# DXP.net
KiCad netlist of a schematic drawn in Altium Designer
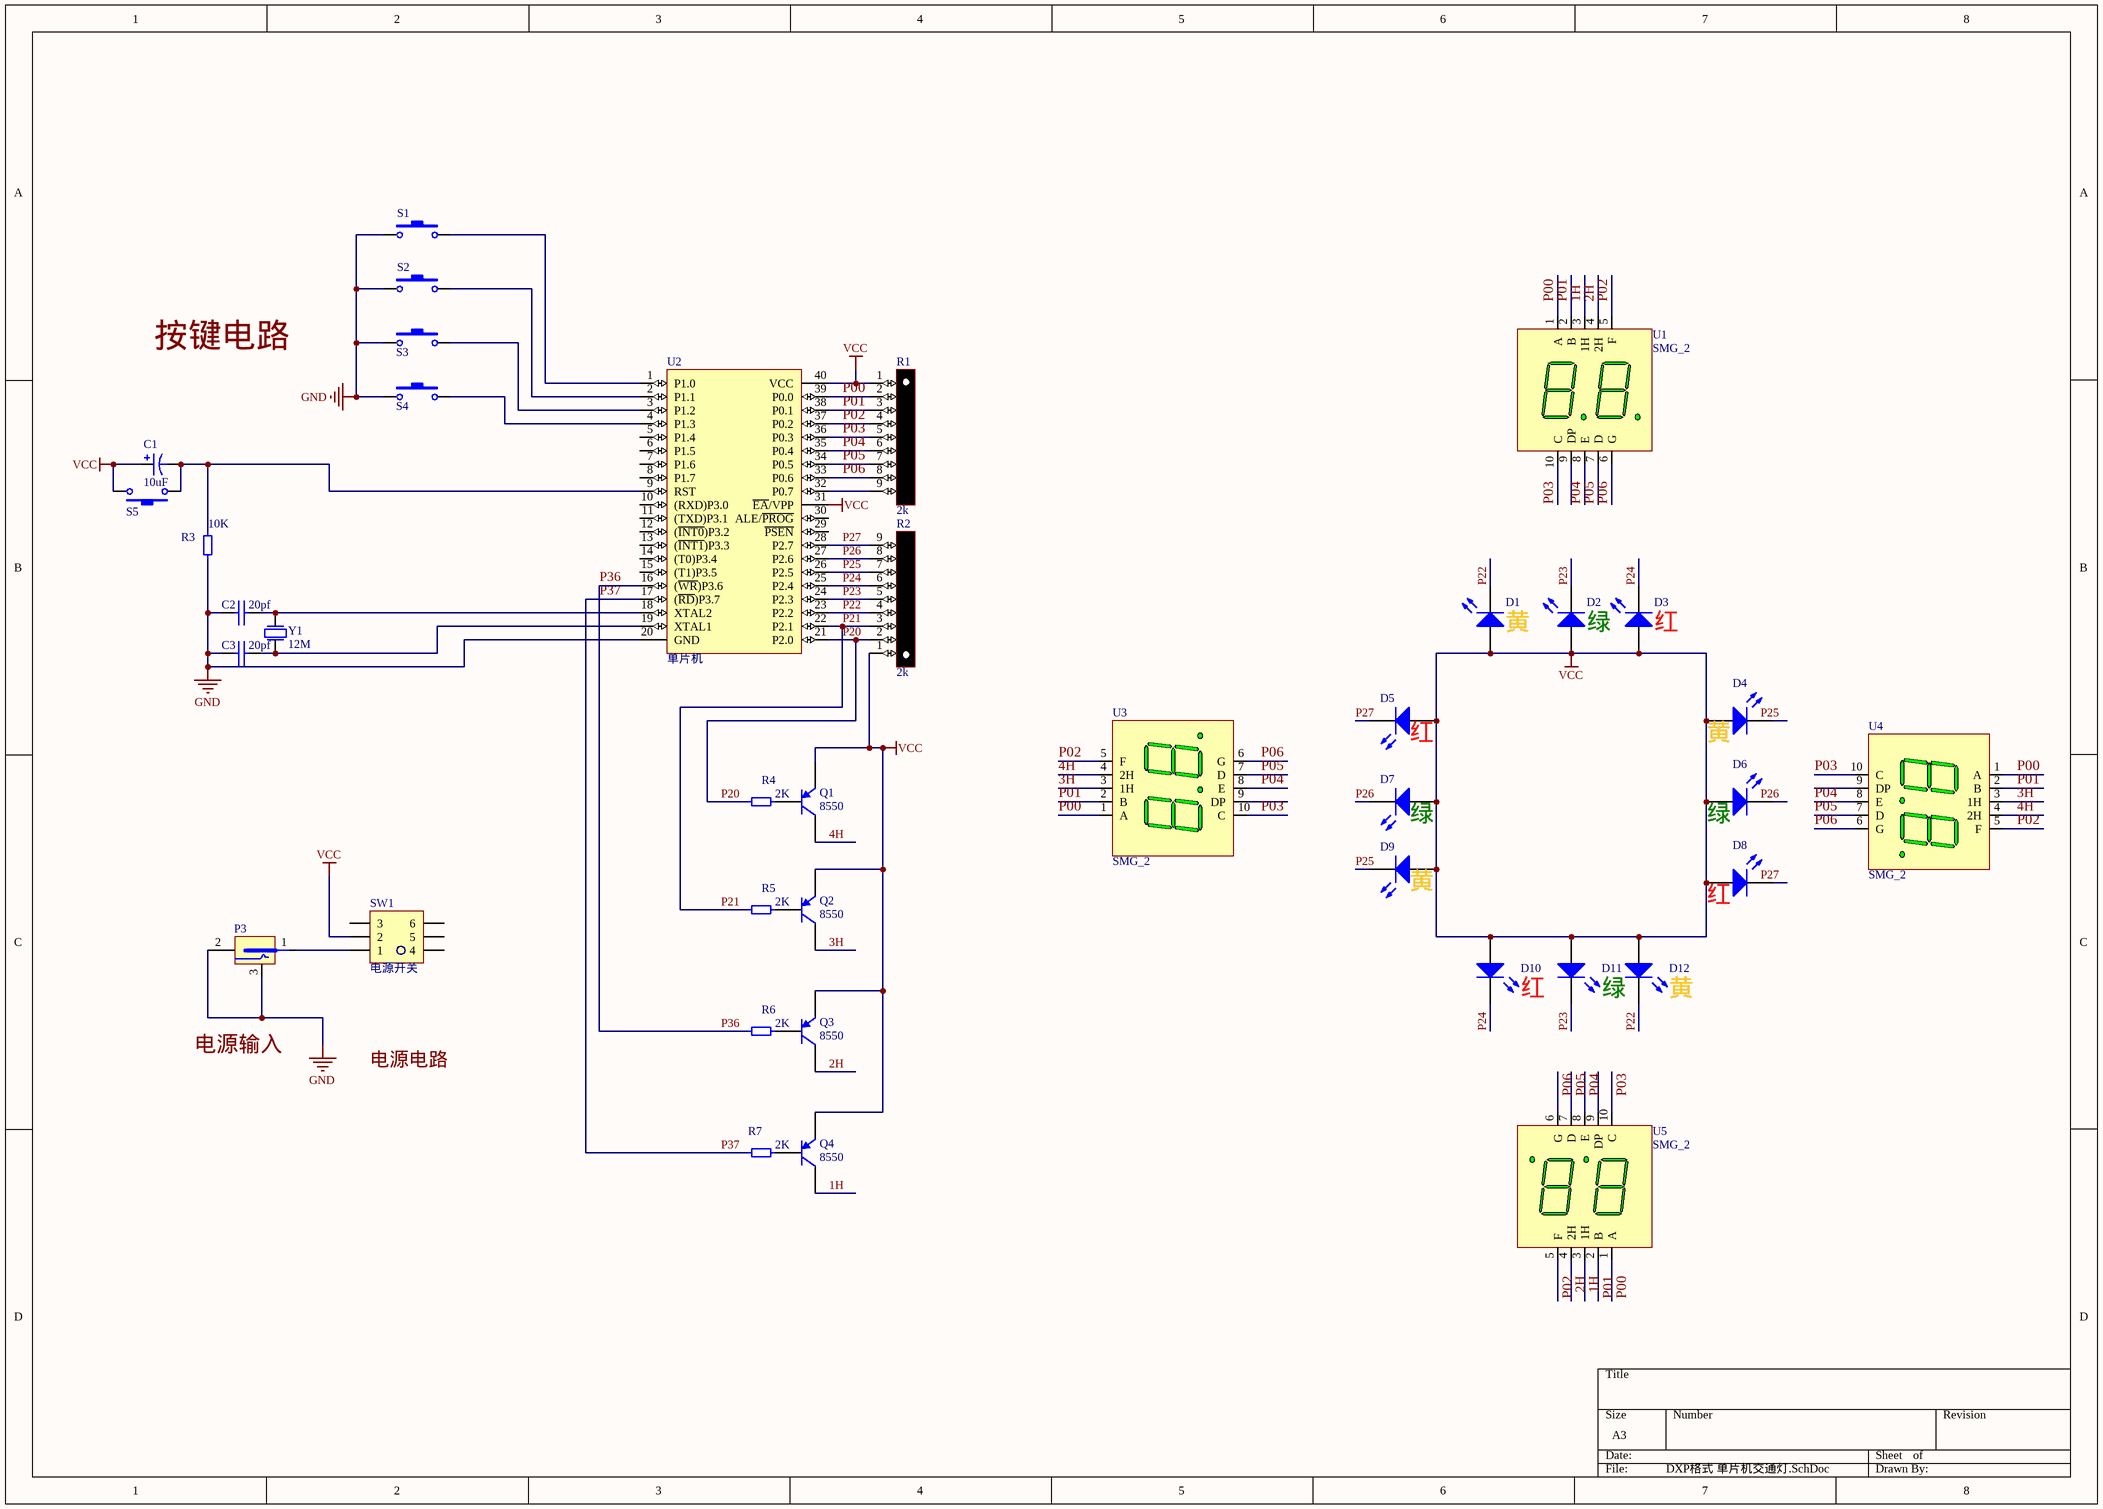
[diagram p0: DXP格式 单片机交通灯.SchDoc]

(export (version "E")
  (design (tool "Eeschema 10.0.6"))
  (components
    (comp (ref "C1")
      (value "10uF")
      (footprint "C_10")
      (description "Polarized Capacitor (Radial)")
      (fields (field (name "PUBLISHER") "Altium Limited"))
      (libsource (lib "简易动环监控系统") (part "Cap Pol1"))
    )
    (comp (ref "C2")
      (value "20pf")
      (footprint "CAP CP")
      (description "电容")
      (libsource (lib "C8051F020最小2") (part "CAP"))
    )
    (comp (ref "C3")
      (value "20pf")
      (footprint "CAP CP")
      (description "电容")
      (libsource (lib "C8051F020最小2") (part "CAP"))
    )
    (comp (ref "D1") (value "黄") (footprint "LED2J") (description "发光二极管") (libsource (lib "亮") (part "LED")))
    (comp (ref "D2") (value "绿") (footprint "LED2J") (description "发光二极管") (libsource (lib "亮") (part "LED")))
    (comp (ref "D3") (value "红") (footprint "LED2J") (description "发光二极管") (libsource (lib "亮") (part "LED")))
    (comp (ref "D4") (value "黄") (footprint "LED2J") (description "发光二极管") (libsource (lib "亮") (part "LED")))
    (comp (ref "D5") (value "红") (footprint "LED2J") (description "发光二极管") (libsource (lib "亮") (part "LED")))
    (comp (ref "D6") (value "绿") (footprint "LED2J") (description "发光二极管") (libsource (lib "亮") (part "LED")))
    (comp (ref "D7") (value "绿") (footprint "LED2J") (description "发光二极管") (libsource (lib "亮") (part "LED")))
    (comp (ref "D8") (value "红") (footprint "LED2J") (description "发光二极管") (libsource (lib "亮") (part "LED")))
    (comp (ref "D9") (value "黄") (footprint "LED2J") (description "发光二极管") (libsource (lib "亮") (part "LED")))
    (comp (ref "D10")
      (value "红")
      (footprint "LED2J")
      (description "发光二极管")
      (libsource (lib "亮") (part "LED"))
    )
    (comp (ref "D11")
      (value "绿")
      (footprint "LED2J")
      (description "发光二极管")
      (libsource (lib "亮") (part "LED"))
    )
    (comp (ref "D12")
      (value "黄")
      (footprint "LED2J")
      (description "发光二极管")
      (libsource (lib "亮") (part "LED"))
    )
    (comp (ref "P3") (value "电源输入") (footprint "DC2.1") (libsource (lib "我自己的") (part "POWER")))
    (comp (ref "Q1")
      (value "8550")
      (footprint "s三极管直插")
      (description "PNP General Purpose Amplifier")
      (fields (field (name "PUBLISHER") "Altium Limited"))
      (libsource (lib "Miscellaneous Devices") (part "2N3906"))
    )
    (comp (ref "Q2")
      (value "8550")
      (footprint "s三极管直插")
      (description "PNP General Purpose Amplifier")
      (fields (field (name "PUBLISHER") "Altium Limited"))
      (libsource (lib "Miscellaneous Devices") (part "2N3906"))
    )
    (comp (ref "Q3")
      (value "8550")
      (footprint "s三极管直插")
      (description "PNP General Purpose Amplifier")
      (fields (field (name "PUBLISHER") "Altium Limited"))
      (libsource (lib "Miscellaneous Devices") (part "2N3906"))
    )
    (comp (ref "Q4")
      (value "8550")
      (footprint "s三极管直插")
      (description "PNP General Purpose Amplifier")
      (fields (field (name "PUBLISHER") "Altium Limited"))
      (libsource (lib "Miscellaneous Devices") (part "2N3906"))
    )
    (comp (ref "R1") (value "2k") (footprint "SIP9") (description "排阻") (libsource (lib "") (part "RES9_1")))
    (comp (ref "R2") (value "2k") (footprint "SIP9") (description "排阻") (libsource (lib "亮") (part "RES9")))
    (comp (ref "R3") (value "10K") (footprint "AXIAL0.3") (libsource (lib "C8051F020最小2") (part "RES2")))
    (comp (ref "R4") (value "2K") (footprint "AXIAL0.3") (libsource (lib "C8051F020最小2") (part "RES2")))
    (comp (ref "R5") (value "2K") (footprint "AXIAL0.3") (libsource (lib "C8051F020最小2") (part "RES2")))
    (comp (ref "R6") (value "2K") (footprint "AXIAL0.3") (libsource (lib "C8051F020最小2") (part "RES2")))
    (comp (ref "R7") (value "2K") (footprint "AXIAL0.3") (libsource (lib "C8051F020最小2") (part "RES2")))
    (comp (ref "S1")
      (value "SW-PB")
      (footprint "key")
      (description "Switch")
      (fields (field (name "PUBLISHER") "Altium Limited"))
      (libsource (lib "实验板原理图") (part "SW-PB"))
    )
    (comp (ref "S2")
      (value "SW-PB")
      (footprint "key")
      (description "Switch")
      (fields (field (name "PUBLISHER") "Altium Limited"))
      (libsource (lib "实验板原理图") (part "SW-PB"))
    )
    (comp (ref "S3")
      (value "SW-PB")
      (footprint "key")
      (description "Switch")
      (fields (field (name "PUBLISHER") "Altium Limited"))
      (libsource (lib "实验板原理图") (part "SW-PB"))
    )
    (comp (ref "S4")
      (value "SW-PB")
      (footprint "key")
      (description "Switch")
      (fields (field (name "PUBLISHER") "Altium Limited"))
      (libsource (lib "实验板原理图") (part "SW-PB"))
    )
    (comp (ref "S5")
      (value "SW-PB")
      (footprint "key")
      (description "Switch")
      (fields (field (name "PUBLISHER") "Altium Limited"))
      (libsource (lib "实验板原理图") (part "SW-PB"))
    )
    (comp (ref "SW1") (value "电源开关") (footprint "sw_自锁 1") (libsource (lib "我自己的") (part "SW1")))
    (comp (ref "U1") (value "SMG_2") (footprint "SMG_2") (libsource (lib "") (part "SMG_2_2")))
    (comp (ref "U2") (value "单片机") (footprint "DIP40 - 做板") (libsource (lib "实验板原理图") (part "U1")))
    (comp (ref "U3") (value "SMG_2") (footprint "SMG_2") (libsource (lib "") (part "SMG_2_3")))
    (comp (ref "U4") (value "SMG_2") (footprint "SMG_2") (libsource (lib "") (part "SMG_2_1")))
    (comp (ref "U5") (value "SMG_2") (footprint "SMG_2") (libsource (lib "交通灯+上下班高峰调整") (part "SMG_2")))
    (comp (ref "Y1")
      (value "12M")
      (footprint "XTAL")
      (description "Crystal Oscillator")
      (libsource (lib "C8051F020最小2") (part "16M"))
    )
  )
  (nets
    (net (code "1") (name "/1H") (class "Default")
      (node (ref "Q4") (pin "3") (pinfunction "C_3") (pintype "passive"))
      (node (ref "U1") (pin "3") (pinfunction "1H_3") (pintype "passive"))
      (node (ref "U5") (pin "3") (pinfunction "1H_3") (pintype "passive"))
    )
    (net (code "2") (name "/2H") (class "Default")
      (node (ref "Q3") (pin "3") (pinfunction "C_3") (pintype "passive"))
      (node (ref "U1") (pin "4") (pinfunction "2H_4") (pintype "passive"))
      (node (ref "U5") (pin "4") (pinfunction "2H_4") (pintype "passive"))
    )
    (net (code "3") (name "/3H") (class "Default")
      (node (ref "Q2") (pin "3") (pinfunction "C_3") (pintype "passive"))
      (node (ref "U3") (pin "3") (pinfunction "1H_3") (pintype "passive"))
      (node (ref "U4") (pin "3") (pinfunction "1H_3") (pintype "passive"))
    )
    (net (code "4") (name "/4H") (class "Default")
      (node (ref "Q1") (pin "3") (pinfunction "C_3") (pintype "passive"))
      (node (ref "U3") (pin "4") (pinfunction "2H_4") (pintype "passive"))
      (node (ref "U4") (pin "4") (pinfunction "2H_4") (pintype "passive"))
    )
    (net (code "5") (name "/P00") (class "Default")
      (node (ref "R1") (pin "2") (pinfunction "2_2") (pintype "bidirectional"))
      (node (ref "U1") (pin "1") (pinfunction "A_1") (pintype "passive"))
      (node (ref "U2") (pin "39") (pinfunction "P0.0_39") (pintype "bidirectional"))
      (node (ref "U3") (pin "1") (pinfunction "A_1") (pintype "passive"))
      (node (ref "U4") (pin "1") (pinfunction "A_1") (pintype "passive"))
      (node (ref "U5") (pin "1") (pinfunction "A_1") (pintype "passive"))
    )
    (net (code "6") (name "/P01") (class "Default")
      (node (ref "R1") (pin "3") (pinfunction "3_3") (pintype "bidirectional"))
      (node (ref "U1") (pin "2") (pinfunction "B_2") (pintype "passive"))
      (node (ref "U2") (pin "38") (pinfunction "P0.1_38") (pintype "bidirectional"))
      (node (ref "U3") (pin "2") (pinfunction "B_2") (pintype "passive"))
      (node (ref "U4") (pin "2") (pinfunction "B_2") (pintype "passive"))
      (node (ref "U5") (pin "2") (pinfunction "B_2") (pintype "passive"))
    )
    (net (code "7") (name "/P02") (class "Default")
      (node (ref "R1") (pin "4") (pinfunction "4_4") (pintype "bidirectional"))
      (node (ref "U1") (pin "5") (pinfunction "F_5") (pintype "passive"))
      (node (ref "U2") (pin "37") (pinfunction "P0.2_37") (pintype "bidirectional"))
      (node (ref "U3") (pin "5") (pinfunction "F_5") (pintype "passive"))
      (node (ref "U4") (pin "5") (pinfunction "F_5") (pintype "passive"))
      (node (ref "U5") (pin "5") (pinfunction "F_5") (pintype "passive"))
    )
    (net (code "8") (name "/P03") (class "Default")
      (node (ref "R1") (pin "5") (pinfunction "5_5") (pintype "bidirectional"))
      (node (ref "U1") (pin "10") (pinfunction "C_10") (pintype "passive"))
      (node (ref "U2") (pin "36") (pinfunction "P0.3_36") (pintype "bidirectional"))
      (node (ref "U3") (pin "10") (pinfunction "C_10") (pintype "passive"))
      (node (ref "U4") (pin "10") (pinfunction "C_10") (pintype "passive"))
      (node (ref "U5") (pin "10") (pinfunction "C_10") (pintype "passive"))
    )
    (net (code "9") (name "/P04") (class "Default")
      (node (ref "R1") (pin "6") (pinfunction "6_6") (pintype "bidirectional"))
      (node (ref "U1") (pin "8") (pinfunction "E_8") (pintype "passive"))
      (node (ref "U2") (pin "35") (pinfunction "P0.4_35") (pintype "bidirectional"))
      (node (ref "U3") (pin "8") (pinfunction "E_8") (pintype "passive"))
      (node (ref "U4") (pin "8") (pinfunction "E_8") (pintype "passive"))
      (node (ref "U5") (pin "8") (pinfunction "E_8") (pintype "passive"))
    )
    (net (code "10") (name "/P05") (class "Default")
      (node (ref "R1") (pin "7") (pinfunction "7_7") (pintype "bidirectional"))
      (node (ref "U1") (pin "7") (pinfunction "D_7") (pintype "passive"))
      (node (ref "U2") (pin "34") (pinfunction "P0.5_34") (pintype "bidirectional"))
      (node (ref "U3") (pin "7") (pinfunction "D_7") (pintype "passive"))
      (node (ref "U4") (pin "7") (pinfunction "D_7") (pintype "passive"))
      (node (ref "U5") (pin "7") (pinfunction "D_7") (pintype "passive"))
    )
    (net (code "11") (name "/P06") (class "Default")
      (node (ref "R1") (pin "8") (pinfunction "8_8") (pintype "bidirectional"))
      (node (ref "U1") (pin "6") (pinfunction "G_6") (pintype "passive"))
      (node (ref "U2") (pin "33") (pinfunction "P0.6_33") (pintype "bidirectional"))
      (node (ref "U3") (pin "6") (pinfunction "G_6") (pintype "passive"))
      (node (ref "U4") (pin "6") (pinfunction "G_6") (pintype "passive"))
      (node (ref "U5") (pin "6") (pinfunction "G_6") (pintype "passive"))
    )
    (net (code "12") (name "/P20") (class "Default")
      (node (ref "R2") (pin "2") (pinfunction "2_2") (pintype "bidirectional"))
      (node (ref "R2") (pin "3") (pinfunction "3_3") (pintype "bidirectional"))
      (node (ref "R4") (pin "2") (pinfunction "2_2") (pintype "passive"))
      (node (ref "R5") (pin "2") (pinfunction "2_2") (pintype "passive"))
      (node (ref "U2") (pin "21") (pinfunction "P2.0_21") (pintype "bidirectional"))
      (node (ref "U2") (pin "22") (pinfunction "P2.1_22") (pintype "bidirectional"))
    )
    (net (code "13") (name "/P22") (class "Default")
      (node (ref "D1") (pin "2") (pinfunction "K_2") (pintype "passive"))
      (node (ref "D12") (pin "2") (pinfunction "K_2") (pintype "passive"))
      (node (ref "R2") (pin "4") (pinfunction "4_4") (pintype "bidirectional"))
      (node (ref "U2") (pin "23") (pinfunction "P2.2_23") (pintype "bidirectional"))
    )
    (net (code "14") (name "/P23") (class "Default")
      (node (ref "D11") (pin "2") (pinfunction "K_2") (pintype "passive"))
      (node (ref "D2") (pin "2") (pinfunction "K_2") (pintype "passive"))
      (node (ref "R2") (pin "5") (pinfunction "5_5") (pintype "bidirectional"))
      (node (ref "U2") (pin "24") (pinfunction "P2.3_24") (pintype "bidirectional"))
    )
    (net (code "15") (name "/P24") (class "Default")
      (node (ref "D10") (pin "2") (pinfunction "K_2") (pintype "passive"))
      (node (ref "D3") (pin "2") (pinfunction "K_2") (pintype "passive"))
      (node (ref "R2") (pin "6") (pinfunction "6_6") (pintype "bidirectional"))
      (node (ref "U2") (pin "25") (pinfunction "P2.4_25") (pintype "bidirectional"))
    )
    (net (code "16") (name "/P25") (class "Default")
      (node (ref "D9") (pin "2") (pinfunction "K_2") (pintype "passive"))
      (node (ref "R2") (pin "7") (pinfunction "7_7") (pintype "bidirectional"))
      (node (ref "U2") (pin "26") (pinfunction "P2.5_26") (pintype "bidirectional"))
    )
    (net (code "17") (name "/P26") (class "Default")
      (node (ref "D7") (pin "2") (pinfunction "K_2") (pintype "passive"))
      (node (ref "R2") (pin "8") (pinfunction "8_8") (pintype "bidirectional"))
      (node (ref "U2") (pin "27") (pinfunction "P2.6_27") (pintype "bidirectional"))
    )
    (net (code "18") (name "/P27") (class "Default")
      (node (ref "D5") (pin "2") (pinfunction "K_2") (pintype "passive"))
      (node (ref "R2") (pin "9") (pinfunction "9_9") (pintype "bidirectional"))
      (node (ref "U2") (pin "28") (pinfunction "P2.7_28") (pintype "bidirectional"))
    )
    (net (code "19") (name "/P36") (class "Default")
      (node (ref "R6") (pin "2") (pinfunction "2_2") (pintype "passive"))
      (node (ref "R7") (pin "2") (pinfunction "2_2") (pintype "passive"))
      (node (ref "U2") (pin "16") (pinfunction "(~{WR})P3.6_16") (pintype "bidirectional"))
      (node (ref "U2") (pin "17") (pinfunction "(~{RD})P3.7_17") (pintype "bidirectional"))
    )
    (net (code "23") (name "GND") (class "Default")
      (node (ref "C2") (pin "1") (pinfunction "1_1") (pintype "passive"))
      (node (ref "C3") (pin "1") (pinfunction "1_1") (pintype "passive"))
      (node (ref "P3") (pin "2") (pintype "passive"))
      (node (ref "P3") (pin "3") (pintype "passive"))
      (node (ref "R3") (pin "1") (pinfunction "1_1") (pintype "passive"))
      (node (ref "S1") (pin "2") (pinfunction "2_2") (pintype "passive"))
      (node (ref "S2") (pin "2") (pinfunction "2_2") (pintype "passive"))
      (node (ref "S3") (pin "2") (pinfunction "2_2") (pintype "passive"))
      (node (ref "S4") (pin "2") (pinfunction "2_2") (pintype "passive"))
      (node (ref "U2") (pin "20") (pinfunction "GND_20") (pintype "power_in"))
    )
    (net (code "24") (name "Net-(P3-Pad1)") (class "Default")
      (node (ref "P3") (pin "1") (pintype "passive"))
      (node (ref "SW1") (pin "1") (pinfunction "1_1") (pintype "passive"))
    )
    (net (code "25") (name "Net-(Q1-B)") (class "Default")
      (node (ref "Q1") (pin "2") (pinfunction "B_2") (pintype "passive"))
      (node (ref "R4") (pin "1") (pinfunction "1_1") (pintype "passive"))
    )
    (net (code "26") (name "Net-(Q2-B)") (class "Default")
      (node (ref "Q2") (pin "2") (pinfunction "B_2") (pintype "passive"))
      (node (ref "R5") (pin "1") (pinfunction "1_1") (pintype "passive"))
    )
    (net (code "27") (name "Net-(Q3-B)") (class "Default")
      (node (ref "Q3") (pin "2") (pinfunction "B_2") (pintype "passive"))
      (node (ref "R6") (pin "1") (pinfunction "1_1") (pintype "passive"))
    )
    (net (code "28") (name "Net-(Q4-B)") (class "Default")
      (node (ref "Q4") (pin "2") (pinfunction "B_2") (pintype "passive"))
      (node (ref "R7") (pin "1") (pinfunction "1_1") (pintype "passive"))
    )
    (net (code "29") (name "Net-(U2-P0.7)") (class "Default")
      (node (ref "R1") (pin "9") (pinfunction "9_9") (pintype "bidirectional"))
      (node (ref "U2") (pin "32") (pinfunction "P0.7_32") (pintype "bidirectional"))
    )
    (net (code "30") (name "Net-(U2-P1.0)") (class "Default")
      (node (ref "S1") (pin "1") (pinfunction "1_1") (pintype "passive"))
      (node (ref "U2") (pin "1") (pinfunction "P1.0_1") (pintype "bidirectional"))
    )
    (net (code "31") (name "Net-(U2-P1.1)") (class "Default")
      (node (ref "S2") (pin "1") (pinfunction "1_1") (pintype "passive"))
      (node (ref "U2") (pin "2") (pinfunction "P1.1_2") (pintype "bidirectional"))
    )
    (net (code "32") (name "Net-(U2-P1.2)") (class "Default")
      (node (ref "S3") (pin "1") (pinfunction "1_1") (pintype "passive"))
      (node (ref "U2") (pin "3") (pinfunction "P1.2_3") (pintype "bidirectional"))
    )
    (net (code "33") (name "Net-(U2-P1.3)") (class "Default")
      (node (ref "S4") (pin "1") (pinfunction "1_1") (pintype "passive"))
      (node (ref "U2") (pin "4") (pinfunction "P1.3_4") (pintype "bidirectional"))
    )
    (net (code "34") (name "Net-(U2-RST)") (class "Default")
      (node (ref "C1") (pin "2") (pinfunction "2_2") (pintype "passive"))
      (node (ref "R3") (pin "2") (pinfunction "2_2") (pintype "passive"))
      (node (ref "S5") (pin "1") (pinfunction "1_1") (pintype "passive"))
      (node (ref "U2") (pin "9") (pinfunction "RST_9") (pintype "bidirectional"))
    )
    (net (code "35") (name "Net-(U2-XTAL1)") (class "Default")
      (node (ref "C3") (pin "2") (pinfunction "2_2") (pintype "passive"))
      (node (ref "U2") (pin "19") (pinfunction "XTAL1_19") (pintype "bidirectional"))
      (node (ref "Y1") (pin "2") (pinfunction "P2_2") (pintype "passive"))
    )
    (net (code "36") (name "Net-(U2-XTAL2)") (class "Default")
      (node (ref "C2") (pin "2") (pinfunction "2_2") (pintype "passive"))
      (node (ref "U2") (pin "18") (pinfunction "XTAL2_18") (pintype "bidirectional"))
      (node (ref "Y1") (pin "1") (pinfunction "P1_1") (pintype "passive"))
    )
    (net (code "37") (name "VCC") (class "Default")
      (node (ref "C1") (pin "1") (pinfunction "1_1") (pintype "passive"))
      (node (ref "D1") (pin "1") (pinfunction "A_1") (pintype "passive"))
      (node (ref "D10") (pin "1") (pinfunction "A_1") (pintype "passive"))
      (node (ref "D11") (pin "1") (pinfunction "A_1") (pintype "passive"))
      (node (ref "D12") (pin "1") (pinfunction "A_1") (pintype "passive"))
      (node (ref "D2") (pin "1") (pinfunction "A_1") (pintype "passive"))
      (node (ref "D3") (pin "1") (pinfunction "A_1") (pintype "passive"))
      (node (ref "D4") (pin "1") (pinfunction "A_1") (pintype "passive"))
      (node (ref "D5") (pin "1") (pinfunction "A_1") (pintype "passive"))
      (node (ref "D6") (pin "1") (pinfunction "A_1") (pintype "passive"))
      (node (ref "D7") (pin "1") (pinfunction "A_1") (pintype "passive"))
      (node (ref "D8") (pin "1") (pinfunction "A_1") (pintype "passive"))
      (node (ref "D9") (pin "1") (pinfunction "A_1") (pintype "passive"))
      (node (ref "Q1") (pin "1") (pinfunction "E_1") (pintype "passive"))
      (node (ref "Q2") (pin "1") (pinfunction "E_1") (pintype "passive"))
      (node (ref "Q3") (pin "1") (pinfunction "E_1") (pintype "passive"))
      (node (ref "Q4") (pin "1") (pinfunction "E_1") (pintype "passive"))
      (node (ref "R1") (pin "1") (pinfunction "COM_1") (pintype "bidirectional"))
      (node (ref "R2") (pin "1") (pinfunction "COM_1") (pintype "bidirectional"))
      (node (ref "S5") (pin "2") (pinfunction "2_2") (pintype "passive"))
      (node (ref "SW1") (pin "2") (pinfunction "2_2") (pintype "passive"))
      (node (ref "U2") (pin "31") (pinfunction "~{EA}/VPP_31") (pintype "power_in"))
      (node (ref "U2") (pin "40") (pinfunction "VCC_40") (pintype "power_in"))
    )
    (net (code "38") (name "unconnected-(D4-K-Pad2)") (class "Default")
      (node (ref "D4") (pin "2") (pinfunction "K_2") (pintype "passive"))
    )
    (net (code "39") (name "unconnected-(D6-K-Pad2)") (class "Default")
      (node (ref "D6") (pin "2") (pinfunction "K_2") (pintype "passive"))
    )
    (net (code "40") (name "unconnected-(D8-K-Pad2)") (class "Default")
      (node (ref "D8") (pin "2") (pinfunction "K_2") (pintype "passive"))
    )
    (net (code "41") (name "unconnected-(SW1-Pad3)") (class "Default")
      (node (ref "SW1") (pin "3") (pinfunction "3_3") (pintype "passive"))
    )
    (net (code "42") (name "unconnected-(SW1-Pad4)") (class "Default")
      (node (ref "SW1") (pin "4") (pinfunction "4_4") (pintype "passive"))
    )
    (net (code "43") (name "unconnected-(SW1-Pad5)") (class "Default")
      (node (ref "SW1") (pin "5") (pinfunction "5_5") (pintype "passive"))
    )
    (net (code "44") (name "unconnected-(SW1-Pad6)") (class "Default")
      (node (ref "SW1") (pin "6") (pinfunction "6_6") (pintype "passive"))
    )
    (net (code "45") (name "unconnected-(U1-DP-Pad9)") (class "Default")
      (node (ref "U1") (pin "9") (pinfunction "DP_9") (pintype "passive"))
    )
    (net (code "46") (name "unconnected-(U2-(RXD)P3.0-Pad10)") (class "Default")
      (node (ref "U2") (pin "10") (pinfunction "(RXD)P3.0_10") (pintype "bidirectional"))
    )
    (net (code "47") (name "unconnected-(U2-(T0)P3.4-Pad14)") (class "Default")
      (node (ref "U2") (pin "14") (pinfunction "(T0)P3.4_14") (pintype "bidirectional"))
    )
    (net (code "48") (name "unconnected-(U2-(T1)P3.5-Pad15)") (class "Default")
      (node (ref "U2") (pin "15") (pinfunction "(T1)P3.5_15") (pintype "bidirectional"))
    )
    (net (code "49") (name "unconnected-(U2-(TXD)P3.1-Pad11)") (class "Default")
      (node (ref "U2") (pin "11") (pinfunction "(TXD)P3.1_11") (pintype "bidirectional"))
    )
    (net (code "50") (name "unconnected-(U2-(~{INT0})P3.2-Pad12)") (class "Default")
      (node (ref "U2") (pin "12") (pinfunction "(~{INT0})P3.2_12") (pintype "bidirectional"))
    )
    (net (code "51") (name "unconnected-(U2-(~{INT1})P3.3-Pad13)") (class "Default")
      (node (ref "U2") (pin "13") (pinfunction "(~{INT1})P3.3_13") (pintype "bidirectional"))
    )
    (net (code "52") (name "unconnected-(U2-ALE{slash}~{PROG}-Pad30)") (class "Default")
      (node (ref "U2") (pin "30") (pinfunction "ALE/~{PROG}_30") (pintype "bidirectional"))
    )
    (net (code "53") (name "unconnected-(U2-P1.4-Pad5)") (class "Default")
      (node (ref "U2") (pin "5") (pinfunction "P1.4_5") (pintype "bidirectional"))
    )
    (net (code "54") (name "unconnected-(U2-P1.5-Pad6)") (class "Default")
      (node (ref "U2") (pin "6") (pinfunction "P1.5_6") (pintype "bidirectional"))
    )
    (net (code "55") (name "unconnected-(U2-P1.6-Pad7)") (class "Default")
      (node (ref "U2") (pin "7") (pinfunction "P1.6_7") (pintype "bidirectional"))
    )
    (net (code "56") (name "unconnected-(U2-P1.7-Pad8)") (class "Default")
      (node (ref "U2") (pin "8") (pinfunction "P1.7_8") (pintype "bidirectional"))
    )
    (net (code "57") (name "unconnected-(U2-~{PSEN}-Pad29)") (class "Default")
      (node (ref "U2") (pin "29") (pinfunction "~{PSEN}_29") (pintype "bidirectional"))
    )
    (net (code "58") (name "unconnected-(U3-DP-Pad9)") (class "Default")
      (node (ref "U3") (pin "9") (pinfunction "DP_9") (pintype "passive"))
    )
    (net (code "59") (name "unconnected-(U4-DP-Pad9)") (class "Default")
      (node (ref "U4") (pin "9") (pinfunction "DP_9") (pintype "passive"))
    )
    (net (code "60") (name "unconnected-(U5-DP-Pad9)") (class "Default")
      (node (ref "U5") (pin "9") (pinfunction "DP_9") (pintype "passive"))
    )
  )
)
